# max1708circ.net
KiCad netlist of a schematic drawn in EAGLE
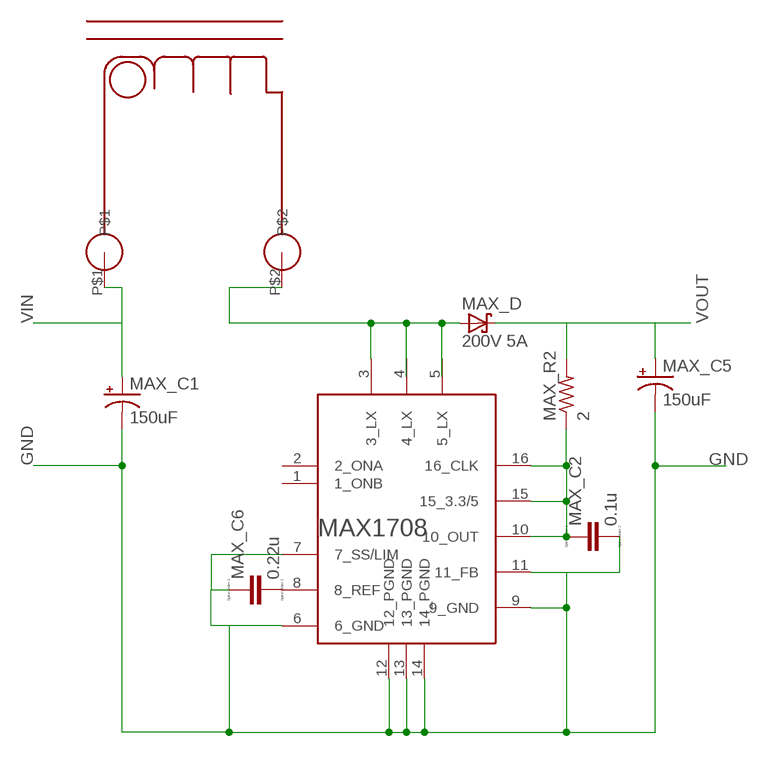
[diagram p0: schematic, sheet 1]

(export (version "E")
  (design (tool "Eeschema 10.0.6"))
  (components
    (comp (ref "MAX_C1")
      (value "150uF")
      (footprint "eagle-import:D_7343-31W")
      (libsource (lib "eagle-import") (part "CPOL-USD/7343-31W"))
    )
    (comp (ref "MAX_C2")
      (value "0.1u")
      (footprint "eagle-import:C1206")
      (libsource (lib "eagle-import") (part "CC1206"))
    )
    (comp (ref "MAX_C5")
      (value "150uF")
      (footprint "eagle-import:D_7343-31W")
      (libsource (lib "eagle-import") (part "CPOL-USD/7343-31W"))
    )
    (comp (ref "MAX_C6")
      (value "0.22u")
      (footprint "eagle-import:C1206")
      (libsource (lib "eagle-import") (part "CC1206"))
    )
    (comp (ref "MAX_D")
      (value "200V 5A")
      (footprint "eagle-import:SMC")
      (libsource (lib "eagle-import") (part "SCHOTTKY-DIODESMC"))
    )
    (comp (ref "MAX_R2")
      (value "2")
      (footprint "eagle-import:R1206")
      (libsource (lib "eagle-import") (part "R-US_R1206"))
    )
    (comp (ref "U$1")
      (value "MAX1708")
      (footprint "eagle-import:QSOP16")
      (libsource (lib "eagle-import") (part "MAX1708"))
    )
    (comp (ref "U$2")
      (value "UP2B-2R2-R")
      (footprint "eagle-import:UP2B-2R2-R")
      (libsource (lib "eagle-import") (part "UP2B-2R2-R"))
    )
  )
  (nets
    (net (code "1") (name "/GND") (class "Default")
      (node (ref "MAX_C1") (pin "-") (pinfunction "-_-") (pintype "passive"))
      (node (ref "MAX_C2") (pin "2") (pinfunction "2_2") (pintype "passive"))
      (node (ref "MAX_C5") (pin "-") (pinfunction "-_-") (pintype "passive"))
      (node (ref "MAX_C6") (pin "1") (pinfunction "1_1") (pintype "passive"))
      (node (ref "U$1") (pin "11") (pinfunction "11_FB_11") (pintype "bidirectional"))
      (node (ref "U$1") (pin "12") (pinfunction "12_PGND_12") (pintype "bidirectional"))
      (node (ref "U$1") (pin "13") (pinfunction "13_PGND_13") (pintype "bidirectional"))
      (node (ref "U$1") (pin "14") (pinfunction "14_PGND_14") (pintype "bidirectional"))
      (node (ref "U$1") (pin "6") (pinfunction "6_GND_6") (pintype "bidirectional"))
      (node (ref "U$1") (pin "7") (pinfunction "7_SS/LIM_7") (pintype "bidirectional"))
      (node (ref "U$1") (pin "9") (pinfunction "9_GND_9") (pintype "bidirectional"))
    )
    (net (code "2") (name "/VIN") (class "Default")
      (node (ref "MAX_C1") (pin "+") (pinfunction "+_+") (pintype "passive"))
      (node (ref "U$2") (pin "P$1") (pinfunction "P$1_P$1") (pintype "bidirectional"))
    )
    (net (code "3") (name "/VOUT") (class "Default")
      (node (ref "MAX_D") (pin "C") (pinfunction "C_C") (pintype "passive"))
      (node (ref "MAX_R2") (pin "2") (pinfunction "2_2") (pintype "passive"))
    )
    (net (code "4") (name "Net-(U$1-3_LX)") (class "Default")
      (node (ref "MAX_D") (pin "A") (pinfunction "A_A") (pintype "passive"))
      (node (ref "U$1") (pin "3") (pinfunction "3_LX_3") (pintype "bidirectional"))
      (node (ref "U$2") (pin "P$2") (pinfunction "P$2_P$2") (pintype "bidirectional"))
    )
    (net (code "5") (name "Net-(U$1-8_REF)") (class "Default")
      (node (ref "MAX_C6") (pin "2") (pinfunction "2_2") (pintype "passive"))
      (node (ref "U$1") (pin "8") (pinfunction "8_REF_8") (pintype "bidirectional"))
    )
    (net (code "6") (name "Net-(U$1-10_OUT)") (class "Default")
      (node (ref "MAX_C2") (pin "1") (pinfunction "1_1") (pintype "passive"))
      (node (ref "MAX_R2") (pin "1") (pinfunction "1_1") (pintype "passive"))
      (node (ref "U$1") (pin "10") (pinfunction "10_OUT_10") (pintype "bidirectional"))
      (node (ref "U$1") (pin "15") (pinfunction "15_3.3/5_15") (pintype "bidirectional"))
      (node (ref "U$1") (pin "16") (pinfunction "16_CLK_16") (pintype "bidirectional"))
    )
    (net (code "7") (name "unconnected-(MAX_C5-Pad+)") (class "Default")
      (node (ref "MAX_C5") (pin "+") (pinfunction "+_+") (pintype "passive"))
    )
    (net (code "8") (name "unconnected-(U$1-1_ONB-Pad1)") (class "Default")
      (node (ref "U$1") (pin "1") (pinfunction "1_ONB_1") (pintype "bidirectional"))
    )
    (net (code "9") (name "unconnected-(U$1-2_ONA-Pad2)") (class "Default")
      (node (ref "U$1") (pin "2") (pinfunction "2_ONA_2") (pintype "bidirectional"))
    )
    (net (code "10") (name "unconnected-(U$1-4_LX-Pad4)") (class "Default")
      (node (ref "U$1") (pin "4") (pinfunction "4_LX_4") (pintype "bidirectional"))
    )
    (net (code "11") (name "unconnected-(U$1-5_LX-Pad5)") (class "Default")
      (node (ref "U$1") (pin "5") (pinfunction "5_LX_5") (pintype "bidirectional"))
    )
  )
)
